# mega-halfshield-MOB.net
KiCad netlist of a schematic drawn in EAGLE
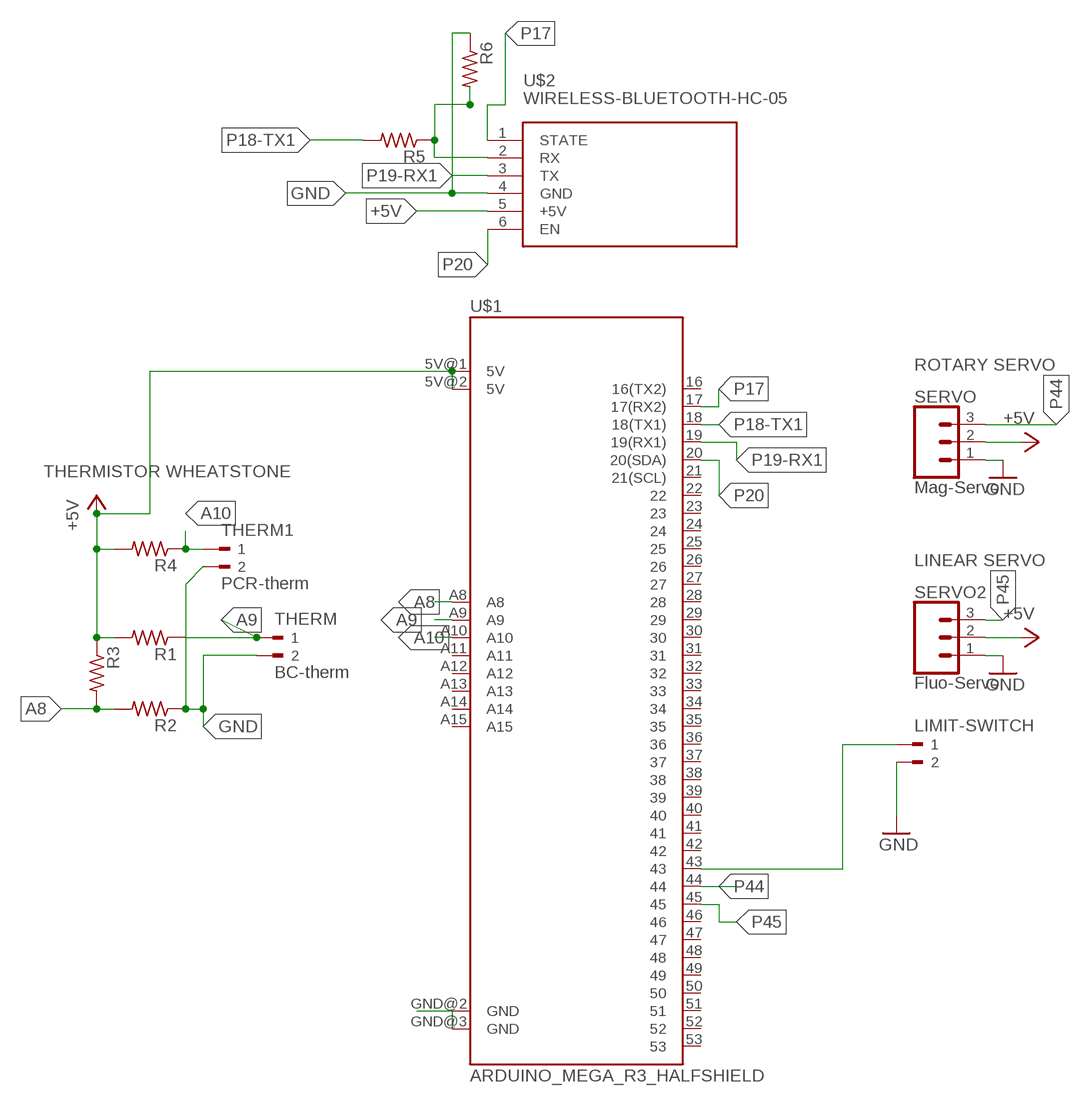
[diagram p0: schematic, sheet 1]

(export (version "E")
  (design (tool "Eeschema 10.0.6"))
  (components
    (comp (ref "LIMIT-SWITCH")
      (value "90-2")
      (footprint "eagle-import:90-2")
      (libsource (lib "eagle-import") (part "90-2"))
    )
    (comp (ref "R1")
      (value "R-US_0309/10")
      (footprint "eagle-import:0309_10")
      (libsource (lib "eagle-import") (part "R-US_0309/10"))
    )
    (comp (ref "R2")
      (value "R-US_0309/10")
      (footprint "eagle-import:0309_10")
      (libsource (lib "eagle-import") (part "R-US_0309/10"))
    )
    (comp (ref "R3")
      (value "R-US_0309/10")
      (footprint "eagle-import:0309_10")
      (libsource (lib "eagle-import") (part "R-US_0309/10"))
    )
    (comp (ref "R4")
      (value "R-US_0309/10")
      (footprint "eagle-import:0309_10")
      (libsource (lib "eagle-import") (part "R-US_0309/10"))
    )
    (comp (ref "R5")
      (value "R-US_0309/10")
      (footprint "eagle-import:0309_10")
      (libsource (lib "eagle-import") (part "R-US_0309/10"))
    )
    (comp (ref "R6")
      (value "R-US_0309/10")
      (footprint "eagle-import:0309_10")
      (libsource (lib "eagle-import") (part "R-US_0309/10"))
    )
    (comp (ref "SERVO")
      (value "Mag-Servo")
      (footprint "eagle-import:1X03")
      (libsource (lib "eagle-import") (part "CONN_03"))
    )
    (comp (ref "SERVO2")
      (value "Fluo-Servo")
      (footprint "eagle-import:1X03")
      (libsource (lib "eagle-import") (part "CONN_03"))
    )
    (comp (ref "THERM")
      (value "BC-therm")
      (footprint "eagle-import:90-2")
      (libsource (lib "eagle-import") (part "90-2"))
    )
    (comp (ref "THERM1")
      (value "PCR-therm")
      (footprint "eagle-import:90-2")
      (libsource (lib "eagle-import") (part "90-2"))
    )
    (comp (ref "U$1")
      (value "ARDUINO_MEGA_R3_HALFSHIELD")
      (footprint "eagle-import:ARDUINO_MEGA_HALFSHIELD")
      (libsource (lib "eagle-import") (part "ARDUINO_MEGA_R3_HALFSHIELD"))
    )
    (comp (ref "U$2")
      (value "WIRELESS-BLUETOOTH-HC-05")
      (footprint "eagle-import:WIRELESS-BLUETOOTH-HC-05")
      (libsource (lib "eagle-import") (part "WIRELESS-BLUETOOTH-HC-05"))
    )
  )
  (nets
    (net (code "1") (name "+5V") (class "Default")
      (node (ref "R1") (pin "2") (pinfunction "2_2") (pintype "passive"))
      (node (ref "R3") (pin "1") (pinfunction "1_1") (pintype "passive"))
      (node (ref "R4") (pin "2") (pinfunction "2_2") (pintype "passive"))
      (node (ref "SERVO") (pin "2") (pinfunction "2_2") (pintype "passive"))
      (node (ref "SERVO2") (pin "2") (pinfunction "2_2") (pintype "passive"))
      (node (ref "U$1") (pin "5V@1") (pinfunction "5V_5V@1") (pintype "bidirectional"))
      (node (ref "U$1") (pin "5V@2") (pinfunction "5V_5V@2") (pintype "bidirectional"))
      (node (ref "U$2") (pin "5") (pinfunction "+5V_5") (pintype "power_in"))
    )
    (net (code "2") (name "A8") (class "Default")
      (node (ref "R2") (pin "2") (pinfunction "2_2") (pintype "passive"))
      (node (ref "R3") (pin "2") (pinfunction "2_2") (pintype "passive"))
      (node (ref "U$1") (pin "A8") (pinfunction "A8_A8") (pintype "bidirectional"))
    )
    (net (code "3") (name "A9") (class "Default")
      (node (ref "R1") (pin "1") (pinfunction "1_1") (pintype "passive"))
      (node (ref "THERM") (pin "1") (pinfunction "1_1") (pintype "passive"))
      (node (ref "U$1") (pin "A9") (pinfunction "A9_A9") (pintype "bidirectional"))
    )
    (net (code "4") (name "A10") (class "Default")
      (node (ref "R4") (pin "1") (pinfunction "1_1") (pintype "passive"))
      (node (ref "THERM1") (pin "1") (pinfunction "1_1") (pintype "passive"))
      (node (ref "U$1") (pin "A10") (pinfunction "A10_A10") (pintype "bidirectional"))
    )
    (net (code "5") (name "GND") (class "Default")
      (node (ref "LIMIT-SWITCH") (pin "2") (pinfunction "2_2") (pintype "passive"))
      (node (ref "R2") (pin "1") (pinfunction "1_1") (pintype "passive"))
      (node (ref "R6") (pin "1") (pinfunction "1_1") (pintype "passive"))
      (node (ref "SERVO") (pin "1") (pinfunction "1_1") (pintype "passive"))
      (node (ref "SERVO2") (pin "1") (pinfunction "1_1") (pintype "passive"))
      (node (ref "THERM") (pin "2") (pinfunction "2_2") (pintype "passive"))
      (node (ref "THERM1") (pin "2") (pinfunction "2_2") (pintype "passive"))
      (node (ref "U$1") (pin "GND@2") (pinfunction "GND_GND@2") (pintype "bidirectional"))
      (node (ref "U$1") (pin "GND@3") (pinfunction "GND_GND@3") (pintype "bidirectional"))
      (node (ref "U$2") (pin "4") (pinfunction "GND_4") (pintype "power_in"))
    )
    (net (code "6") (name "Net-(LIMIT-SWITCH-Pad1)") (class "Default")
      (node (ref "LIMIT-SWITCH") (pin "1") (pinfunction "1_1") (pintype "passive"))
      (node (ref "U$1") (pin "43") (pinfunction "43_43") (pintype "bidirectional"))
    )
    (net (code "7") (name "Net-(U$2-RX)") (class "Default")
      (node (ref "R5") (pin "1") (pinfunction "1_1") (pintype "passive"))
      (node (ref "R6") (pin "2") (pinfunction "2_2") (pintype "passive"))
      (node (ref "U$2") (pin "2") (pinfunction "RX_2") (pintype "bidirectional"))
    )
    (net (code "8") (name "P17") (class "Default")
      (node (ref "U$1") (pin "17") (pinfunction "17(RX2)_17") (pintype "bidirectional"))
      (node (ref "U$2") (pin "1") (pinfunction "STATE_1") (pintype "bidirectional"))
    )
    (net (code "9") (name "P18-TX1") (class "Default")
      (node (ref "R5") (pin "2") (pinfunction "2_2") (pintype "passive"))
      (node (ref "U$1") (pin "18") (pinfunction "18(TX1)_18") (pintype "bidirectional"))
    )
    (net (code "10") (name "P19-RX1") (class "Default")
      (node (ref "U$1") (pin "19") (pinfunction "19(RX1)_19") (pintype "bidirectional"))
      (node (ref "U$2") (pin "3") (pinfunction "TX_3") (pintype "bidirectional"))
    )
    (net (code "11") (name "P20") (class "Default")
      (node (ref "U$1") (pin "20") (pinfunction "20(SDA)_20") (pintype "bidirectional"))
      (node (ref "U$2") (pin "6") (pinfunction "EN_6") (pintype "bidirectional"))
    )
    (net (code "12") (name "P44") (class "Default")
      (node (ref "SERVO") (pin "3") (pinfunction "3_3") (pintype "passive"))
      (node (ref "U$1") (pin "44") (pinfunction "44_44") (pintype "bidirectional"))
    )
    (net (code "13") (name "P45") (class "Default")
      (node (ref "SERVO2") (pin "3") (pinfunction "3_3") (pintype "passive"))
      (node (ref "U$1") (pin "45") (pinfunction "45_45") (pintype "bidirectional"))
    )
    (net (code "14") (name "unconnected-(U$1-16(TX2)-Pad16)") (class "Default")
      (node (ref "U$1") (pin "16") (pinfunction "16(TX2)_16") (pintype "bidirectional"))
    )
    (net (code "15") (name "unconnected-(U$1-21(SCL)-Pad21)") (class "Default")
      (node (ref "U$1") (pin "21") (pinfunction "21(SCL)_21") (pintype "bidirectional"))
    )
    (net (code "16") (name "unconnected-(U$1-Pad22)") (class "Default")
      (node (ref "U$1") (pin "22") (pinfunction "22_22") (pintype "bidirectional"))
    )
    (net (code "17") (name "unconnected-(U$1-Pad23)") (class "Default")
      (node (ref "U$1") (pin "23") (pinfunction "23_23") (pintype "bidirectional"))
    )
    (net (code "18") (name "unconnected-(U$1-Pad24)") (class "Default")
      (node (ref "U$1") (pin "24") (pinfunction "24_24") (pintype "bidirectional"))
    )
    (net (code "19") (name "unconnected-(U$1-Pad25)") (class "Default")
      (node (ref "U$1") (pin "25") (pinfunction "25_25") (pintype "bidirectional"))
    )
    (net (code "20") (name "unconnected-(U$1-Pad26)") (class "Default")
      (node (ref "U$1") (pin "26") (pinfunction "26_26") (pintype "bidirectional"))
    )
    (net (code "21") (name "unconnected-(U$1-Pad27)") (class "Default")
      (node (ref "U$1") (pin "27") (pinfunction "27_27") (pintype "bidirectional"))
    )
    (net (code "22") (name "unconnected-(U$1-Pad28)") (class "Default")
      (node (ref "U$1") (pin "28") (pinfunction "28_28") (pintype "bidirectional"))
    )
    (net (code "23") (name "unconnected-(U$1-Pad29)") (class "Default")
      (node (ref "U$1") (pin "29") (pinfunction "29_29") (pintype "bidirectional"))
    )
    (net (code "24") (name "unconnected-(U$1-Pad30)") (class "Default")
      (node (ref "U$1") (pin "30") (pinfunction "30_30") (pintype "bidirectional"))
    )
    (net (code "25") (name "unconnected-(U$1-Pad31)") (class "Default")
      (node (ref "U$1") (pin "31") (pinfunction "31_31") (pintype "bidirectional"))
    )
    (net (code "26") (name "unconnected-(U$1-Pad32)") (class "Default")
      (node (ref "U$1") (pin "32") (pinfunction "32_32") (pintype "bidirectional"))
    )
    (net (code "27") (name "unconnected-(U$1-Pad33)") (class "Default")
      (node (ref "U$1") (pin "33") (pinfunction "33_33") (pintype "bidirectional"))
    )
    (net (code "28") (name "unconnected-(U$1-Pad34)") (class "Default")
      (node (ref "U$1") (pin "34") (pinfunction "34_34") (pintype "bidirectional"))
    )
    (net (code "29") (name "unconnected-(U$1-Pad35)") (class "Default")
      (node (ref "U$1") (pin "35") (pinfunction "35_35") (pintype "bidirectional"))
    )
    (net (code "30") (name "unconnected-(U$1-Pad36)") (class "Default")
      (node (ref "U$1") (pin "36") (pinfunction "36_36") (pintype "bidirectional"))
    )
    (net (code "31") (name "unconnected-(U$1-Pad37)") (class "Default")
      (node (ref "U$1") (pin "37") (pinfunction "37_37") (pintype "bidirectional"))
    )
    (net (code "32") (name "unconnected-(U$1-Pad38)") (class "Default")
      (node (ref "U$1") (pin "38") (pinfunction "38_38") (pintype "bidirectional"))
    )
    (net (code "33") (name "unconnected-(U$1-Pad39)") (class "Default")
      (node (ref "U$1") (pin "39") (pinfunction "39_39") (pintype "bidirectional"))
    )
    (net (code "34") (name "unconnected-(U$1-Pad40)") (class "Default")
      (node (ref "U$1") (pin "40") (pinfunction "40_40") (pintype "bidirectional"))
    )
    (net (code "35") (name "unconnected-(U$1-Pad41)") (class "Default")
      (node (ref "U$1") (pin "41") (pinfunction "41_41") (pintype "bidirectional"))
    )
    (net (code "36") (name "unconnected-(U$1-Pad42)") (class "Default")
      (node (ref "U$1") (pin "42") (pinfunction "42_42") (pintype "bidirectional"))
    )
    (net (code "37") (name "unconnected-(U$1-Pad46)") (class "Default")
      (node (ref "U$1") (pin "46") (pinfunction "46_46") (pintype "bidirectional"))
    )
    (net (code "38") (name "unconnected-(U$1-Pad47)") (class "Default")
      (node (ref "U$1") (pin "47") (pinfunction "47_47") (pintype "bidirectional"))
    )
    (net (code "39") (name "unconnected-(U$1-Pad48)") (class "Default")
      (node (ref "U$1") (pin "48") (pinfunction "48_48") (pintype "bidirectional"))
    )
    (net (code "40") (name "unconnected-(U$1-Pad49)") (class "Default")
      (node (ref "U$1") (pin "49") (pinfunction "49_49") (pintype "bidirectional"))
    )
    (net (code "41") (name "unconnected-(U$1-Pad50)") (class "Default")
      (node (ref "U$1") (pin "50") (pinfunction "50_50") (pintype "bidirectional"))
    )
    (net (code "42") (name "unconnected-(U$1-Pad51)") (class "Default")
      (node (ref "U$1") (pin "51") (pinfunction "51_51") (pintype "bidirectional"))
    )
    (net (code "43") (name "unconnected-(U$1-Pad52)") (class "Default")
      (node (ref "U$1") (pin "52") (pinfunction "52_52") (pintype "bidirectional"))
    )
    (net (code "44") (name "unconnected-(U$1-Pad53)") (class "Default")
      (node (ref "U$1") (pin "53") (pinfunction "53_53") (pintype "bidirectional"))
    )
    (net (code "45") (name "unconnected-(U$1-PadA11)") (class "Default")
      (node (ref "U$1") (pin "A11") (pinfunction "A11_A11") (pintype "bidirectional"))
    )
    (net (code "46") (name "unconnected-(U$1-PadA12)") (class "Default")
      (node (ref "U$1") (pin "A12") (pinfunction "A12_A12") (pintype "bidirectional"))
    )
    (net (code "47") (name "unconnected-(U$1-PadA13)") (class "Default")
      (node (ref "U$1") (pin "A13") (pinfunction "A13_A13") (pintype "bidirectional"))
    )
    (net (code "48") (name "unconnected-(U$1-PadA14)") (class "Default")
      (node (ref "U$1") (pin "A14") (pinfunction "A14_A14") (pintype "bidirectional"))
    )
    (net (code "49") (name "unconnected-(U$1-PadA15)") (class "Default")
      (node (ref "U$1") (pin "A15") (pinfunction "A15_A15") (pintype "bidirectional"))
    )
  )
)
